# MiniWhip.net
KiCad netlist of a schematic drawn in EAGLE
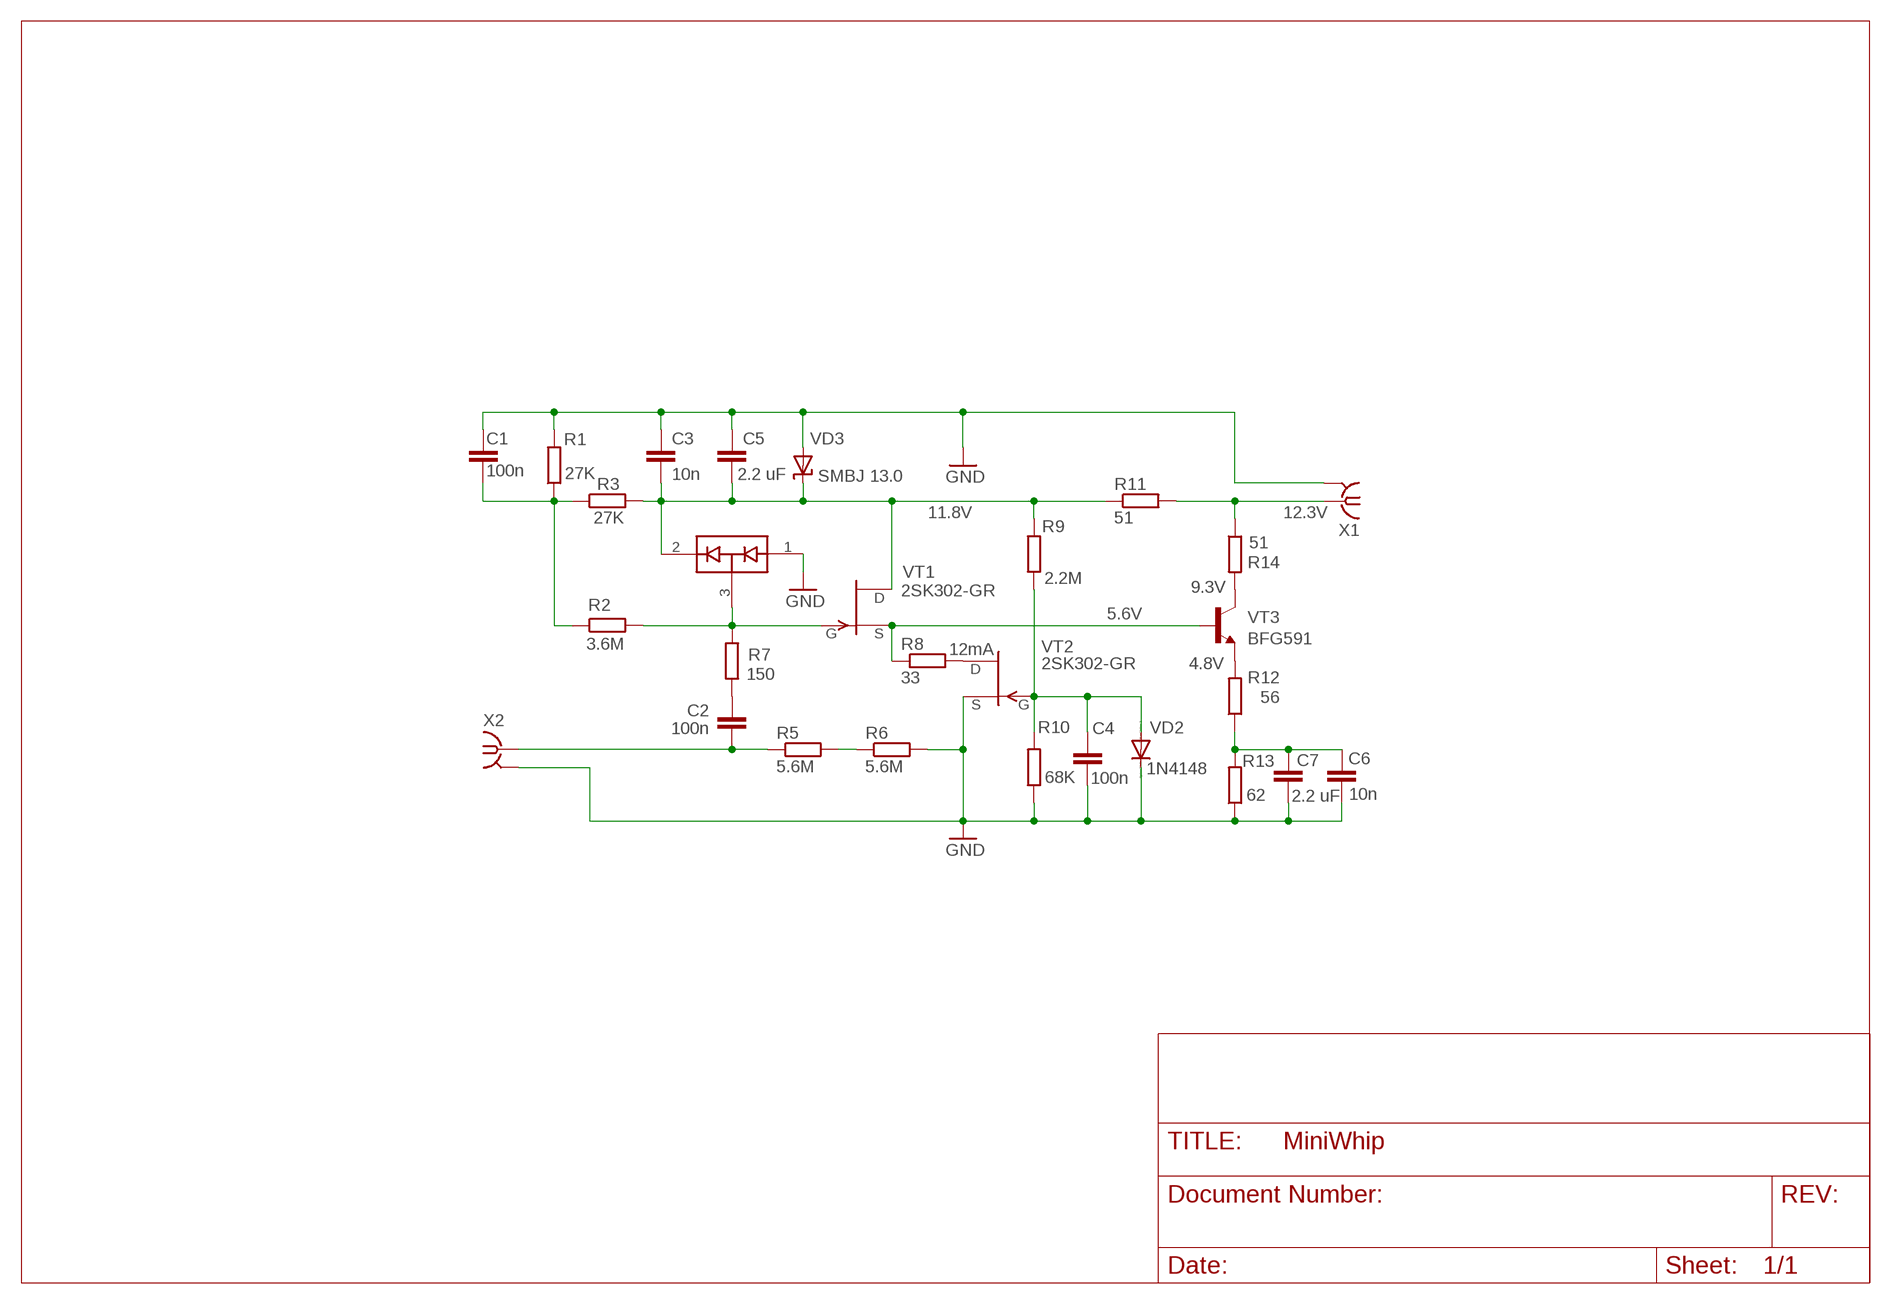
[diagram p0: schematic, sheet 1]

(export (version "E")
  (design (tool "Eeschema 10.0.6"))
  (components
    (comp (ref "C1")
      (value "100n")
      (footprint "eagle-import:C0603")
      (libsource (lib "eagle-import") (part "C-EUC0603"))
    )
    (comp (ref "C2")
      (value "100n")
      (footprint "eagle-import:C0603")
      (libsource (lib "eagle-import") (part "C-EUC0603"))
    )
    (comp (ref "C3")
      (value "10n")
      (footprint "eagle-import:C0603")
      (libsource (lib "eagle-import") (part "C-EUC0603"))
    )
    (comp (ref "C4")
      (value "100n")
      (footprint "eagle-import:C0603")
      (libsource (lib "eagle-import") (part "C-EUC0603"))
    )
    (comp (ref "C5")
      (value "2.2 uF")
      (footprint "eagle-import:C0603")
      (libsource (lib "eagle-import") (part "C-EUC0603"))
    )
    (comp (ref "C6")
      (value "10n")
      (footprint "eagle-import:C0603")
      (libsource (lib "eagle-import") (part "C-EUC0603"))
    )
    (comp (ref "C7")
      (value "2.2 uF")
      (footprint "eagle-import:C0603")
      (libsource (lib "eagle-import") (part "C-EUC0603"))
    )
    (comp (ref "R1")
      (value "27K")
      (footprint "eagle-import:R0603")
      (libsource (lib "eagle-import") (part "R-EU_R0603"))
    )
    (comp (ref "R2")
      (value "3.6M")
      (footprint "eagle-import:R0805")
      (libsource (lib "eagle-import") (part "R-EU_R0805"))
    )
    (comp (ref "R3")
      (value "27K")
      (footprint "eagle-import:R0603")
      (libsource (lib "eagle-import") (part "R-EU_R0603"))
    )
    (comp (ref "R5")
      (value "5.6M")
      (footprint "eagle-import:R0805")
      (libsource (lib "eagle-import") (part "R-EU_R0805"))
    )
    (comp (ref "R6")
      (value "5.6M")
      (footprint "eagle-import:R0805")
      (libsource (lib "eagle-import") (part "R-EU_R0805"))
    )
    (comp (ref "R7")
      (value "150")
      (footprint "eagle-import:R0805")
      (libsource (lib "eagle-import") (part "R-EU_R0805"))
    )
    (comp (ref "R8")
      (value "33")
      (footprint "eagle-import:R0805")
      (libsource (lib "eagle-import") (part "R-EU_R0805"))
    )
    (comp (ref "R9")
      (value "2.2M")
      (footprint "eagle-import:R0603")
      (libsource (lib "eagle-import") (part "R-EU_R0603"))
    )
    (comp (ref "R10")
      (value "68K")
      (footprint "eagle-import:R0603")
      (libsource (lib "eagle-import") (part "R-EU_R0603"))
    )
    (comp (ref "R11")
      (value "51")
      (footprint "eagle-import:R0603")
      (libsource (lib "eagle-import") (part "R-EU_R0603"))
    )
    (comp (ref "R12")
      (value "56")
      (footprint "eagle-import:R0603")
      (libsource (lib "eagle-import") (part "R-EU_R0603"))
    )
    (comp (ref "R13")
      (value "62")
      (footprint "eagle-import:R0603")
      (libsource (lib "eagle-import") (part "R-EU_R0603"))
    )
    (comp (ref "R14")
      (value "51")
      (footprint "eagle-import:R0603")
      (libsource (lib "eagle-import") (part "R-EU_R0603"))
    )
    (comp (ref "VD1")
      (value "BAV99")
      (footprint "eagle-import:SOT23")
      (libsource (lib "eagle-import") (part "BAV99"))
    )
    (comp (ref "VD2")
      (value "1N4148")
      (footprint "eagle-import:SOD80C")
      (libsource (lib "eagle-import") (part "DIODE-SOD80C"))
    )
    (comp (ref "VD3")
      (value "SMBJ 13.0")
      (footprint "eagle-import:SMBJ")
      (libsource (lib "eagle-import") (part "SUPPRESSOR-SMBJ"))
    )
    (comp (ref "VT1")
      (value "2SK302SOT23")
      (footprint "eagle-import:SOT23")
      (libsource (lib "eagle-import") (part "2SK302SOT23"))
    )
    (comp (ref "VT2")
      (value "2SK302SOT23")
      (footprint "eagle-import:SOT23")
      (libsource (lib "eagle-import") (part "2SK302SOT23"))
    )
    (comp (ref "VT3")
      (value "BFG591")
      (footprint "eagle-import:SOT223")
      (libsource (lib "eagle-import") (part "BFG591"))
    )
    (comp (ref "X1")
      (value "SMA-142-0701-801/806")
      (footprint "eagle-import:J502-ND-142-0701-801_806")
      (fields (field (name "MF") "JOHNSON COMPONENTS") (field (name "MPN") "142-0701-801"))
      (libsource (lib "eagle-import") (part "SMA-142-0701-801/806"))
    )
    (comp (ref "X2")
      (value "SMA-142-0701-801/806")
      (footprint "eagle-import:J502-ND-142-0701-801_806")
      (fields (field (name "MF") "JOHNSON COMPONENTS") (field (name "MPN") "142-0701-801"))
      (libsource (lib "eagle-import") (part "SMA-142-0701-801/806"))
    )
  )
  (nets
    (net (code "1") (name "GND") (class "Default")
      (node (ref "C1") (pin "1") (pinfunction "1_1") (pintype "passive"))
      (node (ref "C3") (pin "1") (pinfunction "1_1") (pintype "passive"))
      (node (ref "C4") (pin "2") (pinfunction "2_2") (pintype "passive"))
      (node (ref "C5") (pin "1") (pinfunction "1_1") (pintype "passive"))
      (node (ref "C6") (pin "2") (pinfunction "2_2") (pintype "passive"))
      (node (ref "C7") (pin "2") (pinfunction "2_2") (pintype "passive"))
      (node (ref "R1") (pin "2") (pinfunction "2_2") (pintype "passive"))
      (node (ref "R10") (pin "1") (pinfunction "1_1") (pintype "passive"))
      (node (ref "R13") (pin "1") (pinfunction "1_1") (pintype "passive"))
      (node (ref "R6") (pin "2") (pinfunction "2_2") (pintype "passive"))
      (node (ref "VD1") (pin "1") (pinfunction "A1_1") (pintype "bidirectional"))
      (node (ref "VD2") (pin "C") (pinfunction "C_C") (pintype "passive"))
      (node (ref "VD3") (pin "A") (pinfunction "A_A") (pintype "passive"))
      (node (ref "VT2") (pin "3") (pinfunction "S_3") (pintype "passive"))
      (node (ref "X1") (pin "G@1") (pinfunction "2_G@1") (pintype "passive"))
      (node (ref "X1") (pin "G@2") (pinfunction "2_G@2") (pintype "passive"))
      (node (ref "X1") (pin "G@3") (pinfunction "2_G@3") (pintype "passive"))
      (node (ref "X1") (pin "G@4") (pinfunction "2_G@4") (pintype "passive"))
      (node (ref "X2") (pin "G@1") (pinfunction "2_G@1") (pintype "passive"))
      (node (ref "X2") (pin "G@2") (pinfunction "2_G@2") (pintype "passive"))
      (node (ref "X2") (pin "G@3") (pinfunction "2_G@3") (pintype "passive"))
      (node (ref "X2") (pin "G@4") (pinfunction "2_G@4") (pintype "passive"))
    )
    (net (code "2") (name "Net-(C1-Pad2)") (class "Default")
      (node (ref "C1") (pin "2") (pinfunction "2_2") (pintype "passive"))
      (node (ref "R1") (pin "1") (pinfunction "1_1") (pintype "passive"))
      (node (ref "R2") (pin "1") (pinfunction "1_1") (pintype "passive"))
      (node (ref "R3") (pin "1") (pinfunction "1_1") (pintype "passive"))
    )
    (net (code "3") (name "Net-(C2-Pad1)") (class "Default")
      (node (ref "C2") (pin "1") (pinfunction "1_1") (pintype "passive"))
      (node (ref "R7") (pin "2") (pinfunction "2_2") (pintype "passive"))
    )
    (net (code "4") (name "Net-(C2-Pad2)") (class "Default")
      (node (ref "C2") (pin "2") (pinfunction "2_2") (pintype "passive"))
      (node (ref "R5") (pin "1") (pinfunction "1_1") (pintype "passive"))
      (node (ref "X2") (pin "1") (pinfunction "1_1") (pintype "passive"))
    )
    (net (code "5") (name "Net-(C6-Pad1)") (class "Default")
      (node (ref "C6") (pin "1") (pinfunction "1_1") (pintype "passive"))
      (node (ref "C7") (pin "1") (pinfunction "1_1") (pintype "passive"))
      (node (ref "R12") (pin "1") (pinfunction "1_1") (pintype "passive"))
      (node (ref "R13") (pin "2") (pinfunction "2_2") (pintype "passive"))
    )
    (net (code "6") (name "Net-(R5-Pad2)") (class "Default")
      (node (ref "R5") (pin "2") (pinfunction "2_2") (pintype "passive"))
      (node (ref "R6") (pin "1") (pinfunction "1_1") (pintype "passive"))
    )
    (net (code "7") (name "Net-(R11-Pad2)") (class "Default")
      (node (ref "R11") (pin "2") (pinfunction "2_2") (pintype "passive"))
      (node (ref "R14") (pin "1") (pinfunction "1_1") (pintype "passive"))
      (node (ref "X1") (pin "1") (pinfunction "1_1") (pintype "passive"))
    )
    (net (code "8") (name "Net-(R12-Pad2)") (class "Default")
      (node (ref "R12") (pin "2") (pinfunction "2_2") (pintype "passive"))
      (node (ref "VT3") (pin "1") (pinfunction "E_1") (pintype "passive"))
      (node (ref "VT3") (pin "3") (pinfunction "E_3") (pintype "passive"))
    )
    (net (code "9") (name "Net-(VD1-C2)") (class "Default")
      (node (ref "C3") (pin "2") (pinfunction "2_2") (pintype "passive"))
      (node (ref "C5") (pin "2") (pinfunction "2_2") (pintype "passive"))
      (node (ref "R11") (pin "1") (pinfunction "1_1") (pintype "passive"))
      (node (ref "R3") (pin "2") (pinfunction "2_2") (pintype "passive"))
      (node (ref "R9") (pin "2") (pinfunction "2_2") (pintype "passive"))
      (node (ref "VD1") (pin "2") (pinfunction "C2_2") (pintype "bidirectional"))
      (node (ref "VD3") (pin "C") (pinfunction "C_C") (pintype "passive"))
      (node (ref "VT1") (pin "1") (pinfunction "D_1") (pintype "passive"))
    )
    (net (code "10") (name "Net-(VD1-COM)") (class "Default")
      (node (ref "R2") (pin "2") (pinfunction "2_2") (pintype "passive"))
      (node (ref "R7") (pin "1") (pinfunction "1_1") (pintype "passive"))
      (node (ref "VD1") (pin "3") (pinfunction "COM_3") (pintype "bidirectional"))
      (node (ref "VT1") (pin "2") (pinfunction "G_2") (pintype "passive"))
    )
    (net (code "11") (name "Net-(VT1-S)") (class "Default")
      (node (ref "R8") (pin "1") (pinfunction "1_1") (pintype "passive"))
      (node (ref "VT1") (pin "3") (pinfunction "S_3") (pintype "passive"))
      (node (ref "VT3") (pin "2") (pinfunction "B_2") (pintype "passive"))
    )
    (net (code "12") (name "Net-(VT2-D)") (class "Default")
      (node (ref "R8") (pin "2") (pinfunction "2_2") (pintype "passive"))
      (node (ref "VT2") (pin "1") (pinfunction "D_1") (pintype "passive"))
    )
    (net (code "13") (name "Net-(VT2-G)") (class "Default")
      (node (ref "C4") (pin "1") (pinfunction "1_1") (pintype "passive"))
      (node (ref "R10") (pin "2") (pinfunction "2_2") (pintype "passive"))
      (node (ref "R9") (pin "1") (pinfunction "1_1") (pintype "passive"))
      (node (ref "VD2") (pin "A") (pinfunction "A_A") (pintype "passive"))
      (node (ref "VT2") (pin "2") (pinfunction "G_2") (pintype "passive"))
    )
    (net (code "14") (name "Net-(VT3-C)") (class "Default")
      (node (ref "R14") (pin "2") (pinfunction "2_2") (pintype "passive"))
      (node (ref "VT3") (pin "4") (pinfunction "C_4") (pintype "passive"))
    )
  )
)
